# Sheet3.net
KiCad netlist of a schematic drawn in Altium Designer
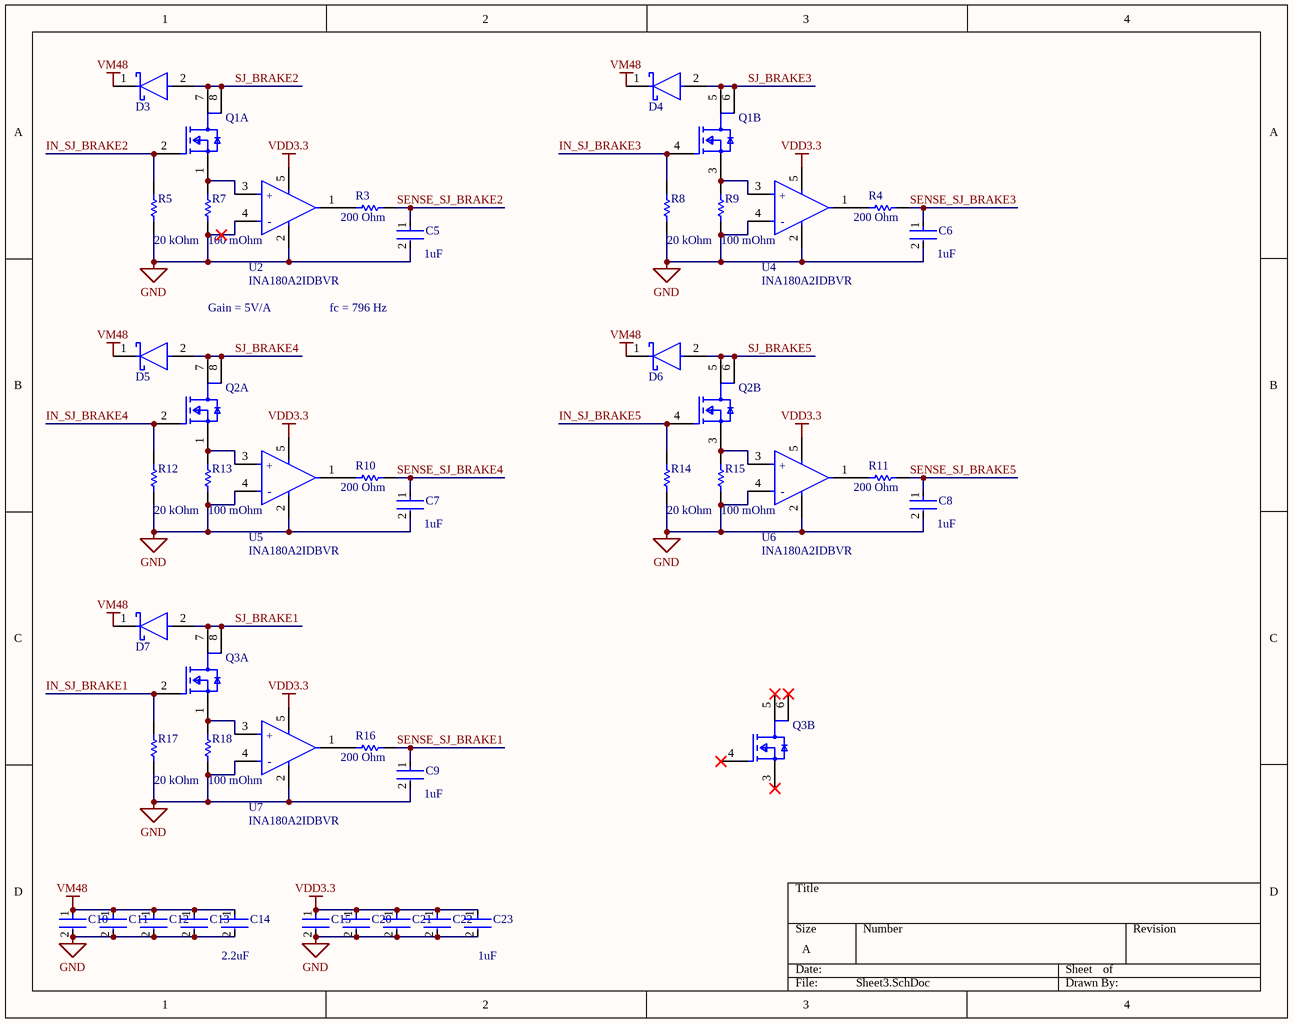
[diagram p0: Sheet3.SchDoc]

(export (version "E")
  (design (tool "Eeschema 10.0.6"))
  (components
    (comp (ref "C5")
      (value "1uF")
      (footprint "FP-GRM15-0_1-MFG")
      (description "CAP CER 1UF 10V X5R 0402")
      (fields
        (field (name "OCTOPART") "https://octopart.com/grm155r61a105ke15d-murata-197442")
        (field (name "MANUFACTURER PART NUMBER") "GRM155R61A105KE15D")
      )
      (libsource (lib "Altium Content Vault") (part "02cd4be3c70576c341d710602a673aa"))
    )
    (comp (ref "C6")
      (value "1uF")
      (footprint "FP-GRM15-0_1-MFG")
      (description "CAP CER 1UF 10V X5R 0402")
      (fields
        (field (name "OCTOPART") "https://octopart.com/grm155r61a105ke15d-murata-197442")
        (field (name "MANUFACTURER PART NUMBER") "GRM155R61A105KE15D")
      )
      (libsource (lib "Altium Content Vault") (part "02cd4be3c70576c341d710602a673aa"))
    )
    (comp (ref "C7")
      (value "1uF")
      (footprint "FP-GRM15-0_1-MFG")
      (description "CAP CER 1UF 10V X5R 0402")
      (fields
        (field (name "OCTOPART") "https://octopart.com/grm155r61a105ke15d-murata-197442")
        (field (name "MANUFACTURER PART NUMBER") "GRM155R61A105KE15D")
      )
      (libsource (lib "Altium Content Vault") (part "02cd4be3c70576c341d710602a673aa"))
    )
    (comp (ref "C8")
      (value "1uF")
      (footprint "FP-GRM15-0_1-MFG")
      (description "CAP CER 1UF 10V X5R 0402")
      (fields
        (field (name "OCTOPART") "https://octopart.com/grm155r61a105ke15d-murata-197442")
        (field (name "MANUFACTURER PART NUMBER") "GRM155R61A105KE15D")
      )
      (libsource (lib "Altium Content Vault") (part "02cd4be3c70576c341d710602a673aa"))
    )
    (comp (ref "C9")
      (value "1uF")
      (footprint "FP-GRM15-0_1-MFG")
      (description "CAP CER 1UF 10V X5R 0402")
      (fields
        (field (name "OCTOPART") "https://octopart.com/grm155r61a105ke15d-murata-197442")
        (field (name "MANUFACTURER PART NUMBER") "GRM155R61A105KE15D")
      )
      (libsource (lib "Altium Content Vault") (part "02cd4be3c70576c341d710602a673aa"))
    )
    (comp (ref "C10")
      (value "12101C225KAT2A")
      (footprint "FP-1210-L_3_3_0_4-W_2_5_0-MFG")
      (description "General Purpose Ceramic Capacitor, 1210, 2.2uF, 10%, X7R, 15%, 100V")
      (fields (field (name "TOLERANCE") "10%") (field (name "VOLTAGE") "100V"))
      (libsource (lib "Altium Content Vault") (part "b4654b650e69147ec39a6b967a45e02"))
    )
    (comp (ref "C11")
      (value "12101C225KAT2A")
      (footprint "FP-1210-L_3_3_0_4-W_2_5_0-MFG")
      (description "General Purpose Ceramic Capacitor, 1210, 2.2uF, 10%, X7R, 15%, 100V")
      (fields (field (name "TOLERANCE") "10%") (field (name "VOLTAGE") "100V"))
      (libsource (lib "Altium Content Vault") (part "b4654b650e69147ec39a6b967a45e02"))
    )
    (comp (ref "C12")
      (value "12101C225KAT2A")
      (footprint "FP-1210-L_3_3_0_4-W_2_5_0-MFG")
      (description "General Purpose Ceramic Capacitor, 1210, 2.2uF, 10%, X7R, 15%, 100V")
      (fields (field (name "TOLERANCE") "10%") (field (name "VOLTAGE") "100V"))
      (libsource (lib "Altium Content Vault") (part "b4654b650e69147ec39a6b967a45e02"))
    )
    (comp (ref "C13")
      (value "12101C225KAT2A")
      (footprint "FP-1210-L_3_3_0_4-W_2_5_0-MFG")
      (description "General Purpose Ceramic Capacitor, 1210, 2.2uF, 10%, X7R, 15%, 100V")
      (fields (field (name "TOLERANCE") "10%") (field (name "VOLTAGE") "100V"))
      (libsource (lib "Altium Content Vault") (part "b4654b650e69147ec39a6b967a45e02"))
    )
    (comp (ref "C14")
      (value "12101C225KAT2A")
      (footprint "FP-1210-L_3_3_0_4-W_2_5_0-MFG")
      (description "General Purpose Ceramic Capacitor, 1210, 2.2uF, 10%, X7R, 15%, 100V")
      (fields
        (field (name "CAPACITANCE") "2.2uF")
        (field (name "TOLERANCE") "10%")
        (field (name "VOLTAGE") "100V")
      )
      (libsource (lib "Altium Content Vault") (part "b4654b650e69147ec39a6b967a45e02"))
    )
    (comp (ref "C15")
      (value "GRM155R61A105KE15D")
      (footprint "FP-GRM15-0_1-MFG")
      (description "CAP CER 1UF 10V X5R 0402")
      (fields
        (field (name "OCTOPART") "https://octopart.com/grm155r61a105ke15d-murata-197442")
        (field (name "MANUFACTURER") "Murata")
      )
      (libsource (lib "Altium Content Vault") (part "02cd4be3c70576c341d710602a673aa"))
    )
    (comp (ref "C20")
      (value "GRM155R61A105KE15D")
      (footprint "FP-GRM15-0_1-MFG")
      (description "CAP CER 1UF 10V X5R 0402")
      (fields
        (field (name "OCTOPART") "https://octopart.com/grm155r61a105ke15d-murata-197442")
        (field (name "MANUFACTURER") "Murata")
      )
      (libsource (lib "Altium Content Vault") (part "02cd4be3c70576c341d710602a673aa"))
    )
    (comp (ref "C21")
      (value "GRM155R61A105KE15D")
      (footprint "FP-GRM15-0_1-MFG")
      (description "CAP CER 1UF 10V X5R 0402")
      (fields
        (field (name "OCTOPART") "https://octopart.com/grm155r61a105ke15d-murata-197442")
        (field (name "MANUFACTURER") "Murata")
      )
      (libsource (lib "Altium Content Vault") (part "02cd4be3c70576c341d710602a673aa"))
    )
    (comp (ref "C22")
      (value "GRM155R61A105KE15D")
      (footprint "FP-GRM15-0_1-MFG")
      (description "CAP CER 1UF 10V X5R 0402")
      (fields
        (field (name "OCTOPART") "https://octopart.com/grm155r61a105ke15d-murata-197442")
        (field (name "MANUFACTURER") "Murata")
      )
      (libsource (lib "Altium Content Vault") (part "02cd4be3c70576c341d710602a673aa"))
    )
    (comp (ref "C23")
      (value "1uF")
      (footprint "FP-GRM15-0_1-MFG")
      (description "CAP CER 1UF 10V X5R 0402")
      (fields
        (field (name "OCTOPART") "https://octopart.com/grm155r61a105ke15d-murata-197442")
        (field (name "MANUFACTURER PART NUMBER") "GRM155R61A105KE15D")
      )
      (libsource (lib "Altium Content Vault") (part "02cd4be3c70576c341d710602a673aa"))
    )
    (comp (ref "D3")
      (value "VS-10MQ100NTRPBF")
      (footprint "FP-95400-MFG")
      (description "DIODE SCHOTTKY 100V 1A SMA")
      (fields
        (field (name "OCTOPART") "https://octopart.com/vs-10mq100ntrpbf-vishay-44340924")
        (field (name "MANUFACTURER") "Vishay")
      )
      (libsource (lib "Altium Content Vault") (part "c1678fac7984e62e0809fbf79c06691"))
    )
    (comp (ref "D4")
      (value "VS-10MQ100NTRPBF")
      (footprint "FP-95400-MFG")
      (description "DIODE SCHOTTKY 100V 1A SMA")
      (fields
        (field (name "OCTOPART") "https://octopart.com/vs-10mq100ntrpbf-vishay-44340924")
        (field (name "MANUFACTURER") "Vishay")
      )
      (libsource (lib "Altium Content Vault") (part "c1678fac7984e62e0809fbf79c06691"))
    )
    (comp (ref "D5")
      (value "VS-10MQ100NTRPBF")
      (footprint "FP-95400-MFG")
      (description "DIODE SCHOTTKY 100V 1A SMA")
      (fields
        (field (name "OCTOPART") "https://octopart.com/vs-10mq100ntrpbf-vishay-44340924")
        (field (name "MANUFACTURER") "Vishay")
      )
      (libsource (lib "Altium Content Vault") (part "c1678fac7984e62e0809fbf79c06691"))
    )
    (comp (ref "D6")
      (value "VS-10MQ100NTRPBF")
      (footprint "FP-95400-MFG")
      (description "DIODE SCHOTTKY 100V 1A SMA")
      (fields
        (field (name "OCTOPART") "https://octopart.com/vs-10mq100ntrpbf-vishay-44340924")
        (field (name "MANUFACTURER") "Vishay")
      )
      (libsource (lib "Altium Content Vault") (part "c1678fac7984e62e0809fbf79c06691"))
    )
    (comp (ref "D7")
      (value "VS-10MQ100NTRPBF")
      (footprint "FP-95400-MFG")
      (description "DIODE SCHOTTKY 100V 1A SMA")
      (fields
        (field (name "OCTOPART") "https://octopart.com/vs-10mq100ntrpbf-vishay-44340924")
        (field (name "MANUFACTURER") "Vishay")
      )
      (libsource (lib "Altium Content Vault") (part "c1678fac7984e62e0809fbf79c06691"))
    )
    (comp (ref "Q1")
      (value "SI4946CDY-T1-GE3")
      (footprint "FP-84021-IPC_B")
      (description "MOSFET N-CHAN DUAL 60V SO-8")
      (fields
        (field (name "OCTOPART") "https://octopart.com/si4946cdy-t1-ge3-vishay-87943198")
        (field (name "MANUFACTURER") "Vishay")
      )
      (libsource (lib "Altium Content Vault") (part "eedecb75c8188e1d7b984da5c9e3b7f"))
    )
    (comp (ref "Q2")
      (value "SI4946CDY-T1-GE3")
      (footprint "FP-84021-IPC_B")
      (description "MOSFET N-CHAN DUAL 60V SO-8")
      (fields
        (field (name "OCTOPART") "https://octopart.com/si4946cdy-t1-ge3-vishay-87943198")
        (field (name "MANUFACTURER") "Vishay")
      )
      (libsource (lib "Altium Content Vault") (part "eedecb75c8188e1d7b984da5c9e3b7f"))
    )
    (comp (ref "Q3")
      (value "SI4946CDY-T1-GE3")
      (footprint "FP-84021-IPC_B")
      (description "MOSFET N-CHAN DUAL 60V SO-8")
      (fields
        (field (name "OCTOPART") "https://octopart.com/si4946cdy-t1-ge3-vishay-87943198")
        (field (name "MANUFACTURER") "Vishay")
      )
      (libsource (lib "Altium Content Vault") (part "eedecb75c8188e1d7b984da5c9e3b7f"))
    )
    (comp (ref "R3")
      (value "200 Ohm")
      (footprint "RESC1005X40X25LL05T10")
      (fields (field (name "MANUFACTURER") "Yageo / Phycomp") (field (name "PART NUMBER") "RC0402FR-07200RL"))
      (libsource (lib "Altium Content Vault") (part "RES"))
    )
    (comp (ref "R4")
      (value "200 Ohm")
      (footprint "RESC1005X40X25LL05T10")
      (fields (field (name "MANUFACTURER") "Yageo / Phycomp") (field (name "PART NUMBER") "RC0402FR-07200RL"))
      (libsource (lib "Altium Content Vault") (part "RES"))
    )
    (comp (ref "R5")
      (value "20 kOhm")
      (footprint "RESC1005X40X25LL05T10")
      (fields (field (name "PART NUMBER") "RC0402FR-0720KL") (field (name "MANUFACTURER") "Yageo / Phycomp"))
      (libsource (lib "Altium Content Vault") (part "RES"))
    )
    (comp (ref "R7")
      (value "100 mOhm")
      (footprint "RESC3216X70X50LL05T20")
      (fields (field (name "PART NUMBER") "ERJ-L08KF10CV") (field (name "MANUFACTURER") "Panasonic"))
      (libsource (lib "Altium Content Vault") (part "RES"))
    )
    (comp (ref "R8")
      (value "20 kOhm")
      (footprint "RESC1005X40X25LL05T10")
      (fields (field (name "PART NUMBER") "RC0402FR-0720KL") (field (name "MANUFACTURER") "Yageo / Phycomp"))
      (libsource (lib "Altium Content Vault") (part "RES"))
    )
    (comp (ref "R9")
      (value "100 mOhm")
      (footprint "RESC3216X70X50LL05T20")
      (fields (field (name "PART NUMBER") "ERJ-L08KF10CV") (field (name "MANUFACTURER") "Panasonic"))
      (libsource (lib "Altium Content Vault") (part "RES"))
    )
    (comp (ref "R10")
      (value "200 Ohm")
      (footprint "RESC1005X40X25LL05T10")
      (fields (field (name "MANUFACTURER") "Yageo / Phycomp") (field (name "PART NUMBER") "RC0402FR-07200RL"))
      (libsource (lib "Altium Content Vault") (part "RES"))
    )
    (comp (ref "R11")
      (value "200 Ohm")
      (footprint "RESC1005X40X25LL05T10")
      (fields (field (name "MANUFACTURER") "Yageo / Phycomp") (field (name "PART NUMBER") "RC0402FR-07200RL"))
      (libsource (lib "Altium Content Vault") (part "RES"))
    )
    (comp (ref "R12")
      (value "20 kOhm")
      (footprint "RESC1005X40X25LL05T10")
      (fields (field (name "PART NUMBER") "RC0402FR-0720KL") (field (name "MANUFACTURER") "Yageo / Phycomp"))
      (libsource (lib "Altium Content Vault") (part "RES"))
    )
    (comp (ref "R13")
      (value "100 mOhm")
      (footprint "RESC3216X70X50LL05T20")
      (fields (field (name "PART NUMBER") "ERJ-L08KF10CV") (field (name "MANUFACTURER") "Panasonic"))
      (libsource (lib "Altium Content Vault") (part "RES"))
    )
    (comp (ref "R14")
      (value "20 kOhm")
      (footprint "RESC1005X40X25LL05T10")
      (fields (field (name "PART NUMBER") "RC0402FR-0720KL") (field (name "MANUFACTURER") "Yageo / Phycomp"))
      (libsource (lib "Altium Content Vault") (part "RES"))
    )
    (comp (ref "R15")
      (value "100 mOhm")
      (footprint "RESC3216X70X50LL05T20")
      (fields (field (name "PART NUMBER") "ERJ-L08KF10CV") (field (name "MANUFACTURER") "Panasonic"))
      (libsource (lib "Altium Content Vault") (part "RES"))
    )
    (comp (ref "R16")
      (value "200 Ohm")
      (footprint "RESC1005X40X25LL05T10")
      (fields (field (name "MANUFACTURER") "Yageo / Phycomp") (field (name "PART NUMBER") "RC0402FR-07200RL"))
      (libsource (lib "Altium Content Vault") (part "RES"))
    )
    (comp (ref "R17")
      (value "20 kOhm")
      (footprint "RESC1005X40X25LL05T10")
      (fields (field (name "PART NUMBER") "RC0402FR-0720KL") (field (name "MANUFACTURER") "Yageo / Phycomp"))
      (libsource (lib "Altium Content Vault") (part "RES"))
    )
    (comp (ref "R18")
      (value "100 mOhm")
      (footprint "RESC3216X70X50LL05T20")
      (fields (field (name "PART NUMBER") "ERJ-L08KF10CV") (field (name "MANUFACTURER") "Panasonic"))
      (libsource (lib "Altium Content Vault") (part "RES"))
    )
    (comp (ref "U2")
      (value "INA180A2IDBVR")
      (footprint "FP-DBV0005A-MFG")
      (description "IC CURR SENSE 1 CIRCUIT SOT23-5")
      (libsource (lib "Altium Content Vault") (part "0a55cf1a948ad01a3239aec1b7efad0"))
    )
    (comp (ref "U4")
      (value "INA180A2IDBVR")
      (footprint "FP-DBV0005A-MFG")
      (description "IC CURR SENSE 1 CIRCUIT SOT23-5")
      (libsource (lib "Altium Content Vault") (part "0a55cf1a948ad01a3239aec1b7efad0"))
    )
    (comp (ref "U5")
      (value "INA180A2IDBVR")
      (footprint "FP-DBV0005A-MFG")
      (description "IC CURR SENSE 1 CIRCUIT SOT23-5")
      (libsource (lib "Altium Content Vault") (part "0a55cf1a948ad01a3239aec1b7efad0"))
    )
    (comp (ref "U6")
      (value "INA180A2IDBVR")
      (footprint "FP-DBV0005A-MFG")
      (description "IC CURR SENSE 1 CIRCUIT SOT23-5")
      (libsource (lib "Altium Content Vault") (part "0a55cf1a948ad01a3239aec1b7efad0"))
    )
    (comp (ref "U7")
      (value "INA180A2IDBVR")
      (footprint "FP-DBV0005A-MFG")
      (description "IC CURR SENSE 1 CIRCUIT SOT23-5")
      (libsource (lib "Altium Content Vault") (part "0a55cf1a948ad01a3239aec1b7efad0"))
    )
  )
  (nets
    (net (code "1") (name "/IN_SJ_BRAKE1") (class "Default")
      (node (ref "Q3") (pin "2") (pinfunction "G1_2") (pintype "passive"))
      (node (ref "R17") (pin "2") (pinfunction "2_2") (pintype "passive"))
    )
    (net (code "2") (name "/IN_SJ_BRAKE2") (class "Default")
      (node (ref "Q1") (pin "2") (pinfunction "G1_2") (pintype "passive"))
      (node (ref "R5") (pin "2") (pinfunction "2_2") (pintype "passive"))
    )
    (net (code "3") (name "/IN_SJ_BRAKE3") (class "Default")
      (node (ref "Q1") (pin "4") (pinfunction "G2_4") (pintype "passive"))
      (node (ref "R8") (pin "2") (pinfunction "2_2") (pintype "passive"))
    )
    (net (code "4") (name "/IN_SJ_BRAKE4") (class "Default")
      (node (ref "Q2") (pin "2") (pinfunction "G1_2") (pintype "passive"))
      (node (ref "R12") (pin "2") (pinfunction "2_2") (pintype "passive"))
    )
    (net (code "5") (name "/IN_SJ_BRAKE5") (class "Default")
      (node (ref "Q2") (pin "4") (pinfunction "G2_4") (pintype "passive"))
      (node (ref "R14") (pin "2") (pinfunction "2_2") (pintype "passive"))
    )
    (net (code "6") (name "/SENSE_SJ_BRAKE1") (class "Default")
      (node (ref "C9") (pin "1") (pinfunction "1_1") (pintype "passive"))
      (node (ref "R16") (pin "2") (pinfunction "2_2") (pintype "passive"))
    )
    (net (code "7") (name "/SENSE_SJ_BRAKE2") (class "Default")
      (node (ref "C5") (pin "1") (pinfunction "1_1") (pintype "passive"))
      (node (ref "R3") (pin "2") (pinfunction "2_2") (pintype "passive"))
    )
    (net (code "8") (name "/SENSE_SJ_BRAKE3") (class "Default")
      (node (ref "C6") (pin "1") (pinfunction "1_1") (pintype "passive"))
      (node (ref "R4") (pin "2") (pinfunction "2_2") (pintype "passive"))
    )
    (net (code "9") (name "/SENSE_SJ_BRAKE4") (class "Default")
      (node (ref "C7") (pin "1") (pinfunction "1_1") (pintype "passive"))
      (node (ref "R10") (pin "2") (pinfunction "2_2") (pintype "passive"))
    )
    (net (code "10") (name "/SENSE_SJ_BRAKE5") (class "Default")
      (node (ref "C8") (pin "1") (pinfunction "1_1") (pintype "passive"))
      (node (ref "R11") (pin "2") (pinfunction "2_2") (pintype "passive"))
    )
    (net (code "11") (name "/SJ_BRAKE1") (class "Default")
      (node (ref "D7") (pin "2") (pinfunction "A_2") (pintype "passive"))
      (node (ref "Q3") (pin "7") (pinfunction "D1_7") (pintype "passive"))
      (node (ref "Q3") (pin "8") (pinfunction "D1_8") (pintype "passive"))
    )
    (net (code "12") (name "/SJ_BRAKE2") (class "Default")
      (node (ref "D3") (pin "2") (pinfunction "A_2") (pintype "passive"))
      (node (ref "Q1") (pin "7") (pinfunction "D1_7") (pintype "passive"))
      (node (ref "Q1") (pin "8") (pinfunction "D1_8") (pintype "passive"))
    )
    (net (code "13") (name "/SJ_BRAKE3") (class "Default")
      (node (ref "D4") (pin "2") (pinfunction "A_2") (pintype "passive"))
      (node (ref "Q1") (pin "5") (pinfunction "D2_5") (pintype "passive"))
      (node (ref "Q1") (pin "6") (pinfunction "D2_6") (pintype "passive"))
    )
    (net (code "14") (name "/SJ_BRAKE4") (class "Default")
      (node (ref "D5") (pin "2") (pinfunction "A_2") (pintype "passive"))
      (node (ref "Q2") (pin "7") (pinfunction "D1_7") (pintype "passive"))
      (node (ref "Q2") (pin "8") (pinfunction "D1_8") (pintype "passive"))
    )
    (net (code "15") (name "/SJ_BRAKE5") (class "Default")
      (node (ref "D6") (pin "2") (pinfunction "A_2") (pintype "passive"))
      (node (ref "Q2") (pin "5") (pinfunction "D2_5") (pintype "passive"))
      (node (ref "Q2") (pin "6") (pinfunction "D2_6") (pintype "passive"))
    )
    (net (code "16") (name "GND") (class "Default")
      (node (ref "C10") (pin "2") (pinfunction "2_2") (pintype "passive"))
      (node (ref "C11") (pin "2") (pinfunction "2_2") (pintype "passive"))
      (node (ref "C12") (pin "2") (pinfunction "2_2") (pintype "passive"))
      (node (ref "C13") (pin "2") (pinfunction "2_2") (pintype "passive"))
      (node (ref "C14") (pin "2") (pinfunction "2_2") (pintype "passive"))
      (node (ref "C15") (pin "2") (pinfunction "2_2") (pintype "passive"))
      (node (ref "C20") (pin "2") (pinfunction "2_2") (pintype "passive"))
      (node (ref "C21") (pin "2") (pinfunction "2_2") (pintype "passive"))
      (node (ref "C22") (pin "2") (pinfunction "2_2") (pintype "passive"))
      (node (ref "C23") (pin "2") (pinfunction "2_2") (pintype "passive"))
      (node (ref "C5") (pin "2") (pinfunction "2_2") (pintype "passive"))
      (node (ref "C6") (pin "2") (pinfunction "2_2") (pintype "passive"))
      (node (ref "C7") (pin "2") (pinfunction "2_2") (pintype "passive"))
      (node (ref "C8") (pin "2") (pinfunction "2_2") (pintype "passive"))
      (node (ref "C9") (pin "2") (pinfunction "2_2") (pintype "passive"))
      (node (ref "R12") (pin "1") (pinfunction "1_1") (pintype "passive"))
      (node (ref "R13") (pin "1") (pinfunction "1_1") (pintype "passive"))
      (node (ref "R14") (pin "1") (pinfunction "1_1") (pintype "passive"))
      (node (ref "R15") (pin "1") (pinfunction "1_1") (pintype "passive"))
      (node (ref "R17") (pin "1") (pinfunction "1_1") (pintype "passive"))
      (node (ref "R18") (pin "1") (pinfunction "1_1") (pintype "passive"))
      (node (ref "R5") (pin "1") (pinfunction "1_1") (pintype "passive"))
      (node (ref "R7") (pin "1") (pinfunction "1_1") (pintype "passive"))
      (node (ref "R8") (pin "1") (pinfunction "1_1") (pintype "passive"))
      (node (ref "R9") (pin "1") (pinfunction "1_1") (pintype "passive"))
      (node (ref "U2") (pin "2") (pinfunction "GND_2") (pintype "power_in"))
      (node (ref "U2") (pin "4") (pinfunction "IN-_4") (pintype "tri_state"))
      (node (ref "U4") (pin "2") (pinfunction "GND_2") (pintype "power_in"))
      (node (ref "U4") (pin "4") (pinfunction "IN-_4") (pintype "tri_state"))
      (node (ref "U5") (pin "2") (pinfunction "GND_2") (pintype "power_in"))
      (node (ref "U5") (pin "4") (pinfunction "IN-_4") (pintype "tri_state"))
      (node (ref "U6") (pin "2") (pinfunction "GND_2") (pintype "power_in"))
      (node (ref "U6") (pin "4") (pinfunction "IN-_4") (pintype "tri_state"))
      (node (ref "U7") (pin "2") (pinfunction "GND_2") (pintype "power_in"))
      (node (ref "U7") (pin "4") (pinfunction "IN-_4") (pintype "tri_state"))
    )
    (net (code "17") (name "Net-(Q1A-S1)") (class "Default")
      (node (ref "Q1") (pin "1") (pinfunction "S1_1") (pintype "passive"))
      (node (ref "R7") (pin "2") (pinfunction "2_2") (pintype "passive"))
      (node (ref "U2") (pin "3") (pinfunction "IN+_3") (pintype "tri_state"))
    )
    (net (code "18") (name "Net-(Q1B-S2)") (class "Default")
      (node (ref "Q1") (pin "3") (pinfunction "S2_3") (pintype "passive"))
      (node (ref "R9") (pin "2") (pinfunction "2_2") (pintype "passive"))
      (node (ref "U4") (pin "3") (pinfunction "IN+_3") (pintype "tri_state"))
    )
    (net (code "19") (name "Net-(Q2A-S1)") (class "Default")
      (node (ref "Q2") (pin "1") (pinfunction "S1_1") (pintype "passive"))
      (node (ref "R13") (pin "2") (pinfunction "2_2") (pintype "passive"))
      (node (ref "U5") (pin "3") (pinfunction "IN+_3") (pintype "tri_state"))
    )
    (net (code "20") (name "Net-(Q2B-S2)") (class "Default")
      (node (ref "Q2") (pin "3") (pinfunction "S2_3") (pintype "passive"))
      (node (ref "R15") (pin "2") (pinfunction "2_2") (pintype "passive"))
      (node (ref "U6") (pin "3") (pinfunction "IN+_3") (pintype "tri_state"))
    )
    (net (code "21") (name "Net-(Q3A-S1)") (class "Default")
      (node (ref "Q3") (pin "1") (pinfunction "S1_1") (pintype "passive"))
      (node (ref "R18") (pin "2") (pinfunction "2_2") (pintype "passive"))
      (node (ref "U7") (pin "3") (pinfunction "IN+_3") (pintype "tri_state"))
    )
    (net (code "22") (name "Net-(U2-OUT)") (class "Default")
      (node (ref "R3") (pin "1") (pinfunction "1_1") (pintype "passive"))
      (node (ref "U2") (pin "1") (pinfunction "OUT_1") (pintype "passive"))
    )
    (net (code "23") (name "Net-(U4-OUT)") (class "Default")
      (node (ref "R4") (pin "1") (pinfunction "1_1") (pintype "passive"))
      (node (ref "U4") (pin "1") (pinfunction "OUT_1") (pintype "passive"))
    )
    (net (code "24") (name "Net-(U5-OUT)") (class "Default")
      (node (ref "R10") (pin "1") (pinfunction "1_1") (pintype "passive"))
      (node (ref "U5") (pin "1") (pinfunction "OUT_1") (pintype "passive"))
    )
    (net (code "25") (name "Net-(U6-OUT)") (class "Default")
      (node (ref "R11") (pin "1") (pinfunction "1_1") (pintype "passive"))
      (node (ref "U6") (pin "1") (pinfunction "OUT_1") (pintype "passive"))
    )
    (net (code "26") (name "Net-(U7-OUT)") (class "Default")
      (node (ref "R16") (pin "1") (pinfunction "1_1") (pintype "passive"))
      (node (ref "U7") (pin "1") (pinfunction "OUT_1") (pintype "passive"))
    )
    (net (code "27") (name "VDD3.3") (class "Default")
      (node (ref "C15") (pin "1") (pinfunction "1_1") (pintype "passive"))
      (node (ref "C20") (pin "1") (pinfunction "1_1") (pintype "passive"))
      (node (ref "C21") (pin "1") (pinfunction "1_1") (pintype "passive"))
      (node (ref "C22") (pin "1") (pinfunction "1_1") (pintype "passive"))
      (node (ref "C23") (pin "1") (pinfunction "1_1") (pintype "passive"))
      (node (ref "U2") (pin "5") (pinfunction "VS_5") (pintype "power_in"))
      (node (ref "U4") (pin "5") (pinfunction "VS_5") (pintype "power_in"))
      (node (ref "U5") (pin "5") (pinfunction "VS_5") (pintype "power_in"))
      (node (ref "U6") (pin "5") (pinfunction "VS_5") (pintype "power_in"))
      (node (ref "U7") (pin "5") (pinfunction "VS_5") (pintype "power_in"))
    )
    (net (code "28") (name "VM48") (class "Default")
      (node (ref "C10") (pin "1") (pinfunction "1_1") (pintype "passive"))
      (node (ref "C11") (pin "1") (pinfunction "1_1") (pintype "passive"))
      (node (ref "C12") (pin "1") (pinfunction "1_1") (pintype "passive"))
      (node (ref "C13") (pin "1") (pinfunction "1_1") (pintype "passive"))
      (node (ref "C14") (pin "1") (pinfunction "1_1") (pintype "passive"))
      (node (ref "D3") (pin "1") (pinfunction "C_1") (pintype "passive"))
      (node (ref "D4") (pin "1") (pinfunction "C_1") (pintype "passive"))
      (node (ref "D5") (pin "1") (pinfunction "C_1") (pintype "passive"))
      (node (ref "D6") (pin "1") (pinfunction "C_1") (pintype "passive"))
      (node (ref "D7") (pin "1") (pinfunction "C_1") (pintype "passive"))
    )
    (net (code "29") (name "unconnected-(Q3B-D2-Pad5)") (class "Default")
      (node (ref "Q3") (pin "5") (pinfunction "D2_5") (pintype "passive+no_connect"))
    )
    (net (code "30") (name "unconnected-(Q3B-D2-Pad6)") (class "Default")
      (node (ref "Q3") (pin "6") (pinfunction "D2_6") (pintype "passive+no_connect"))
    )
    (net (code "31") (name "unconnected-(Q3B-G2-Pad4)") (class "Default")
      (node (ref "Q3") (pin "4") (pinfunction "G2_4") (pintype "passive+no_connect"))
    )
    (net (code "32") (name "unconnected-(Q3B-S2-Pad3)") (class "Default")
      (node (ref "Q3") (pin "3") (pinfunction "S2_3") (pintype "passive+no_connect"))
    )
  )
)
